# 3V3_REG.net
KiCad netlist of a schematic drawn in Altium Designer
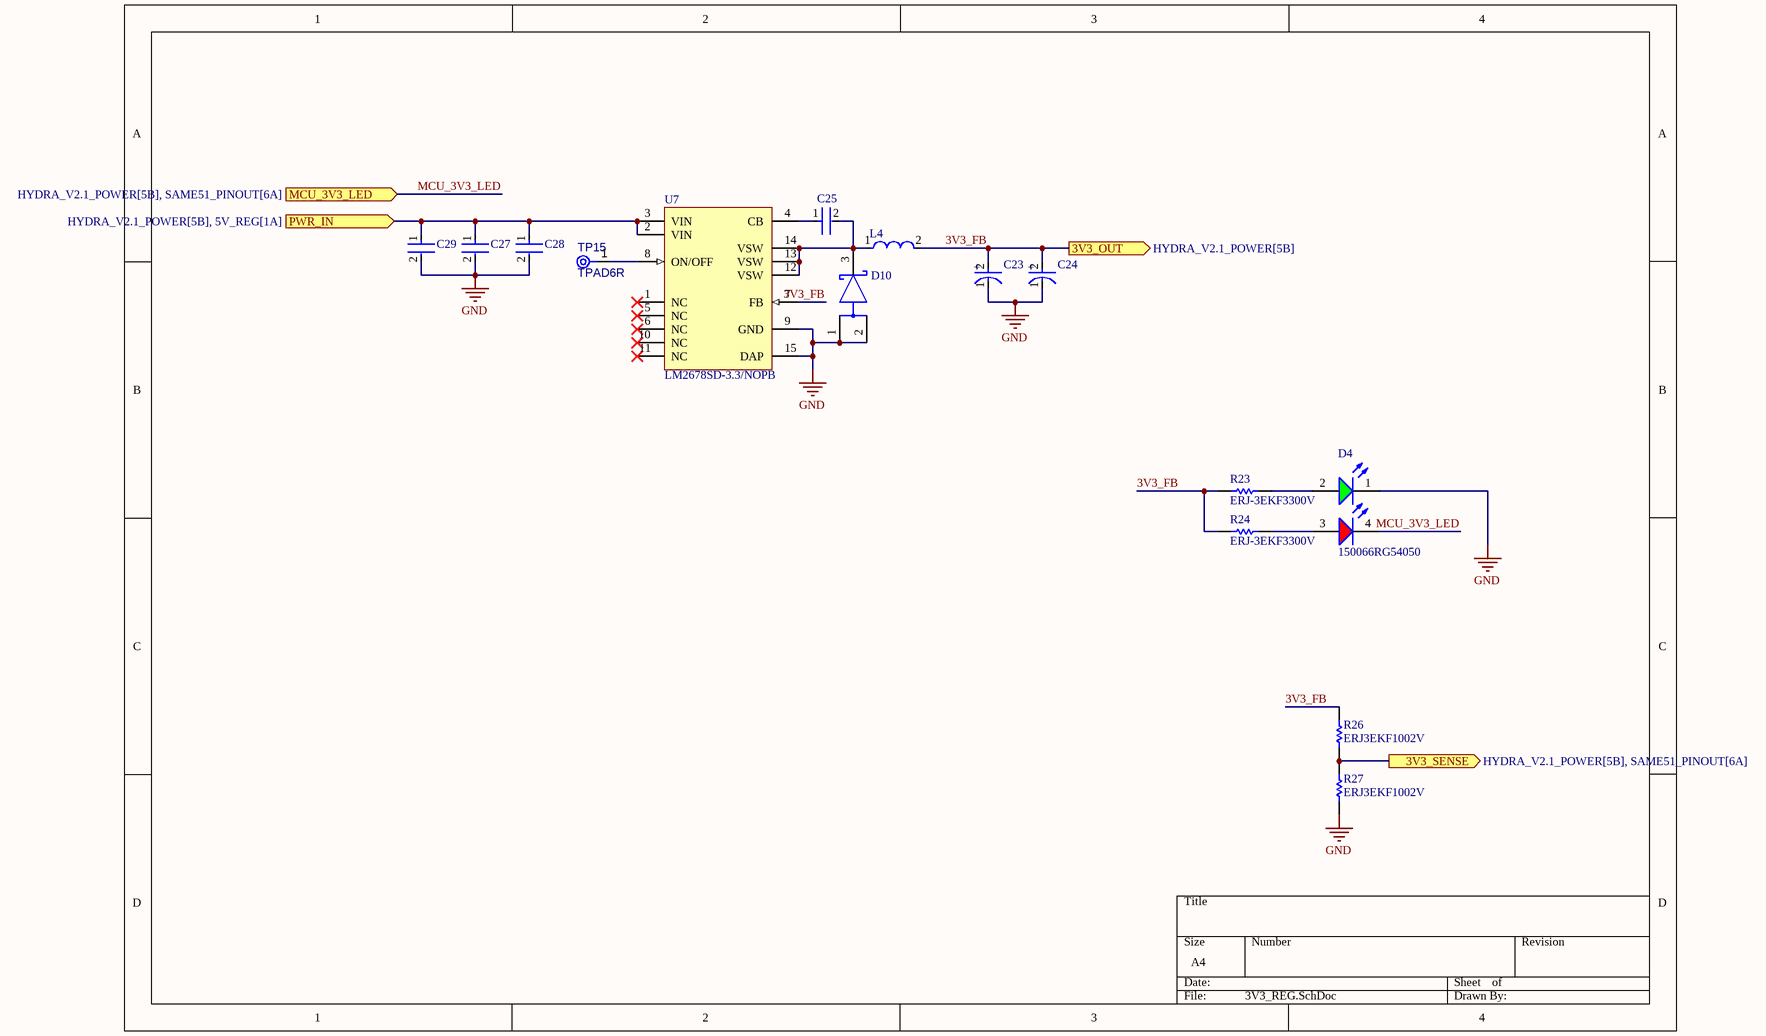
[diagram p0: 3V3_REG.SchDoc]

(export (version "E")
  (design (tool "Eeschema 10.0.6"))
  (components
    (comp (ref "C23")
      (value "10TPC68M")
      (footprint "FP-POSCAP-D2-MFG")
      (description "Molded Tantalum Polymer Capacitor 68uF 20% 10V life 2000Hours SMD 2917")
      (fields (field (name "VOLTAGE") "10V") (field (name "TOLERANCE") "20%"))
      (libsource (lib "Altium Content Vault") (part "a00bbbee19879c290e62620ae7e47b1"))
    )
    (comp (ref "C24")
      (value "10TPC68M")
      (footprint "FP-POSCAP-D2-MFG")
      (description "Molded Tantalum Polymer Capacitor 68uF 20% 10V life 2000Hours SMD 2917")
      (fields (field (name "VOLTAGE") "10V") (field (name "TOLERANCE") "20%"))
      (libsource (lib "Altium Content Vault") (part "a00bbbee19879c290e62620ae7e47b1"))
    )
    (comp (ref "C25")
      (value "C0805C103J5RACTU")
      (footprint "FP-C0805C-DN-MFG")
      (description "CAP CER 10000PF 50V X7R 0805")
      (fields
        (field (name "MANUFACTURER") "KEMET")
        (field (name "OCTOPART") "https://octopart.com/c0805c103j5ractu-kemet-133473")
      )
      (libsource (lib "Altium Content Vault") (part "b4654b650e69147ec39a6b967a45e02"))
    )
    (comp (ref "C27")
      (value "C2012X5R1V156M125AC")
      (footprint "FP-C2012-125-0_2-MFG")
      (description "Multilayer Ceramic Capacitors 15μF ±20% 35V X5R SMD 0805")
      (fields (field (name "TOLERANCE") "20%"))
      (libsource (lib "Altium Content Vault") (part "b4654b650e69147ec39a6b967a45e02"))
    )
    (comp (ref "C28")
      (value "C2012X5R1V156M125AC")
      (footprint "FP-C2012-125-0_2-MFG")
      (description "Multilayer Ceramic Capacitors 15μF ±20% 35V X5R SMD 0805")
      (fields (field (name "TOLERANCE") "20%"))
      (libsource (lib "Altium Content Vault") (part "b4654b650e69147ec39a6b967a45e02"))
    )
    (comp (ref "C29")
      (value "C2012X5R1V156M125AC")
      (footprint "FP-C2012-125-0_2-MFG")
      (description "Multilayer Ceramic Capacitors 15μF ±20% 35V X5R SMD 0805")
      (fields (field (name "TOLERANCE") "20%"))
      (libsource (lib "Altium Content Vault") (part "b4654b650e69147ec39a6b967a45e02"))
    )
    (comp (ref "D4")
      (value "150066RG54050")
      (footprint "WL-SBCD_0606")
      (description "Led, Red/Grn, 180Mcd/230Mcd, 624Nm/525Nm Rohs Compliant: Yes")
      (libsource (lib "uORocketry Hardware") (part "WL-SBCD_0606_Red & Green"))
    )
    (comp (ref "D10")
      (value "SS5P10-M3/86A")
      (footprint "FP-95570-MFG")
      (description "DIODE SCHOTTKY 100V 5A TO277A")
      (libsource (lib "Altium Content Vault") (part "03725f8997c85b601c823eea96032f8"))
    )
    (comp (ref "L4")
      (value "IHLP4040DZER220M11")
      (footprint "FP-IHLP-4040DZ-FP_3_124x3-MFG")
      (description "Commercial Inductors, Low DCR Series 22uH 5A 66mΩ 20%")
      (fields (field (name "TOLERANCE") "20%"))
      (libsource (lib "Altium Content Vault") (part "725321dda6339637d4d059423bc1c3c"))
    )
    (comp (ref "R23")
      (value "ERJ-3EKF3300V")
      (footprint "RESC1608X55X30LL15T15")
      (description "Chip Resistor, 330 Ohm, +/- 1%, 0.1 W, -55 to 155 degC, 0603 (1608 Metric), RoHS, Tape and Reel")
      (libsource (lib "Altium Content Vault") (part "RES-2"))
    )
    (comp (ref "R24")
      (value "ERJ-3EKF3300V")
      (footprint "RESC1608X55X30LL15T15")
      (description "Chip Resistor, 330 Ohm, +/- 1%, 0.1 W, -55 to 155 degC, 0603 (1608 Metric), RoHS, Tape and Reel")
      (libsource (lib "Altium Content Vault") (part "RES-2"))
    )
    (comp (ref "R26")
      (value "ERJ3EKF1002V")
      (footprint "RESC1609X55X30LL15T15")
      (description "Chip Resistor, 10 KOhm, +/- 1%, 0.1 W, -55 to 155 degC, 0603 (1608 Metric), RoHS, Tape and Reel")
      (fields (field (name "TOLERANCE") "1%") (field (name "MANUFACTURER") "Panasonic"))
      (libsource (lib "Altium Content Vault") (part "RES-2"))
    )
    (comp (ref "R27")
      (value "ERJ3EKF1002V")
      (footprint "RESC1609X55X30LL15T15")
      (description "Chip Resistor, 10 KOhm, +/- 1%, 0.1 W, -55 to 155 degC, 0603 (1608 Metric), RoHS, Tape and Reel")
      (fields (field (name "TOLERANCE") "1%") (field (name "MANUFACTURER") "Panasonic"))
      (libsource (lib "Altium Content Vault") (part "RES-2"))
    )
    (comp (ref "TP15")
      (value "TPAD6R")
      (footprint "TP06R")
      (description "0.6mm round")
      (libsource (lib "uORocketry Hardware") (part "CMP-001-0001-4"))
    )
    (comp (ref "U7")
      (value "LM2678SD-3.3/NOPB")
      (footprint "NHM0014A_V")
      (description "SIMPLE SWITCHER® High Efficiency 5A Step-Down Voltage Regulator, 14-pin LLP, Pb-Free")
      (fields (field (name "MANUFACTURER") "Texas Instruments"))
      (libsource (lib "Altium Content Vault") (part "PM-REG-LM2678SD"))
    )
  )
  (nets
    (net (code "1") (name "/3V3_FB") (class "Default")
      (node (ref "C23") (pin "2") (pinfunction "A_2") (pintype "passive"))
      (node (ref "C24") (pin "2") (pinfunction "A_2") (pintype "passive"))
      (node (ref "L4") (pin "2") (pinfunction "2_2") (pintype "passive"))
      (node (ref "R23") (pin "1") (pinfunction "1_1") (pintype "passive"))
      (node (ref "R24") (pin "1") (pinfunction "1_1") (pintype "passive"))
      (node (ref "R26") (pin "2") (pinfunction "2_2") (pintype "passive"))
      (node (ref "U7") (pin "7") (pinfunction "FB_7") (pintype "input"))
    )
    (net (code "2") (name "/3V3_SENSE") (class "Default")
      (node (ref "R26") (pin "1") (pinfunction "1_1") (pintype "passive"))
      (node (ref "R27") (pin "2") (pinfunction "2_2") (pintype "passive"))
    )
    (net (code "3") (name "/MCU_3V3_LED") (class "Default")
      (node (ref "D4") (pin "4") (pinfunction "K_4") (pintype "passive"))
    )
    (net (code "4") (name "/PWR_IN") (class "Default")
      (node (ref "C27") (pin "1") (pinfunction "1_1") (pintype "passive"))
      (node (ref "C28") (pin "1") (pinfunction "1_1") (pintype "passive"))
      (node (ref "C29") (pin "1") (pinfunction "1_1") (pintype "passive"))
      (node (ref "U7") (pin "2") (pinfunction "VIN_2") (pintype "power_in"))
      (node (ref "U7") (pin "3") (pinfunction "VIN_3") (pintype "power_in"))
    )
    (net (code "5") (name "GND") (class "Default")
      (node (ref "C23") (pin "1") (pinfunction "C_1") (pintype "passive"))
      (node (ref "C24") (pin "1") (pinfunction "C_1") (pintype "passive"))
      (node (ref "C27") (pin "2") (pinfunction "2_2") (pintype "passive"))
      (node (ref "C28") (pin "2") (pinfunction "2_2") (pintype "passive"))
      (node (ref "C29") (pin "2") (pinfunction "2_2") (pintype "passive"))
      (node (ref "D10") (pin "1") (pinfunction "A_1") (pintype "passive"))
      (node (ref "D10") (pin "2") (pinfunction "A_2") (pintype "passive"))
      (node (ref "D4") (pin "1") (pinfunction "K_1") (pintype "passive"))
      (node (ref "R27") (pin "1") (pinfunction "1_1") (pintype "passive"))
      (node (ref "U7") (pin "15") (pinfunction "DAP_15") (pintype "power_in"))
      (node (ref "U7") (pin "9") (pinfunction "GND_9") (pintype "power_in"))
    )
    (net (code "6") (name "Net-(D4-A-Pad2)") (class "Default")
      (node (ref "D4") (pin "2") (pinfunction "A_2") (pintype "passive"))
      (node (ref "R23") (pin "2") (pinfunction "2_2") (pintype "passive"))
    )
    (net (code "7") (name "Net-(D4-A-Pad3)") (class "Default")
      (node (ref "D4") (pin "3") (pinfunction "A_3") (pintype "passive"))
      (node (ref "R24") (pin "2") (pinfunction "2_2") (pintype "passive"))
    )
    (net (code "8") (name "Net-(D10-C)") (class "Default")
      (node (ref "C25") (pin "2") (pinfunction "2_2") (pintype "passive"))
      (node (ref "D10") (pin "3") (pinfunction "C_3") (pintype "passive"))
      (node (ref "L4") (pin "1") (pinfunction "1_1") (pintype "passive"))
      (node (ref "U7") (pin "12") (pinfunction "VSW_12") (pintype "power_in"))
      (node (ref "U7") (pin "13") (pinfunction "VSW_13") (pintype "power_in"))
      (node (ref "U7") (pin "14") (pinfunction "VSW_14") (pintype "power_in"))
    )
    (net (code "9") (name "Net-(TP15-TP)") (class "Default")
      (node (ref "TP15") (pin "1") (pinfunction "TP_1") (pintype "passive"))
      (node (ref "U7") (pin "8") (pinfunction "ON/OFF_8") (pintype "input"))
    )
    (net (code "10") (name "Net-(U7-CB)") (class "Default")
      (node (ref "C25") (pin "1") (pinfunction "1_1") (pintype "passive"))
      (node (ref "U7") (pin "4") (pinfunction "CB_4") (pintype "passive"))
    )
    (net (code "11") (name "unconnected-(U7-NC-Pad1)") (class "Default")
      (node (ref "U7") (pin "1") (pinfunction "NC_1") (pintype "passive+no_connect"))
    )
    (net (code "12") (name "unconnected-(U7-NC-Pad5)") (class "Default")
      (node (ref "U7") (pin "5") (pinfunction "NC_5") (pintype "passive+no_connect"))
    )
    (net (code "13") (name "unconnected-(U7-NC-Pad6)") (class "Default")
      (node (ref "U7") (pin "6") (pinfunction "NC_6") (pintype "passive+no_connect"))
    )
    (net (code "14") (name "unconnected-(U7-NC-Pad10)") (class "Default")
      (node (ref "U7") (pin "10") (pinfunction "NC_10") (pintype "passive+no_connect"))
    )
    (net (code "15") (name "unconnected-(U7-NC-Pad11)") (class "Default")
      (node (ref "U7") (pin "11") (pinfunction "NC_11") (pintype "passive+no_connect"))
    )
  )
)
